# Sensors.net
KiCad netlist of a schematic drawn in Altium Designer
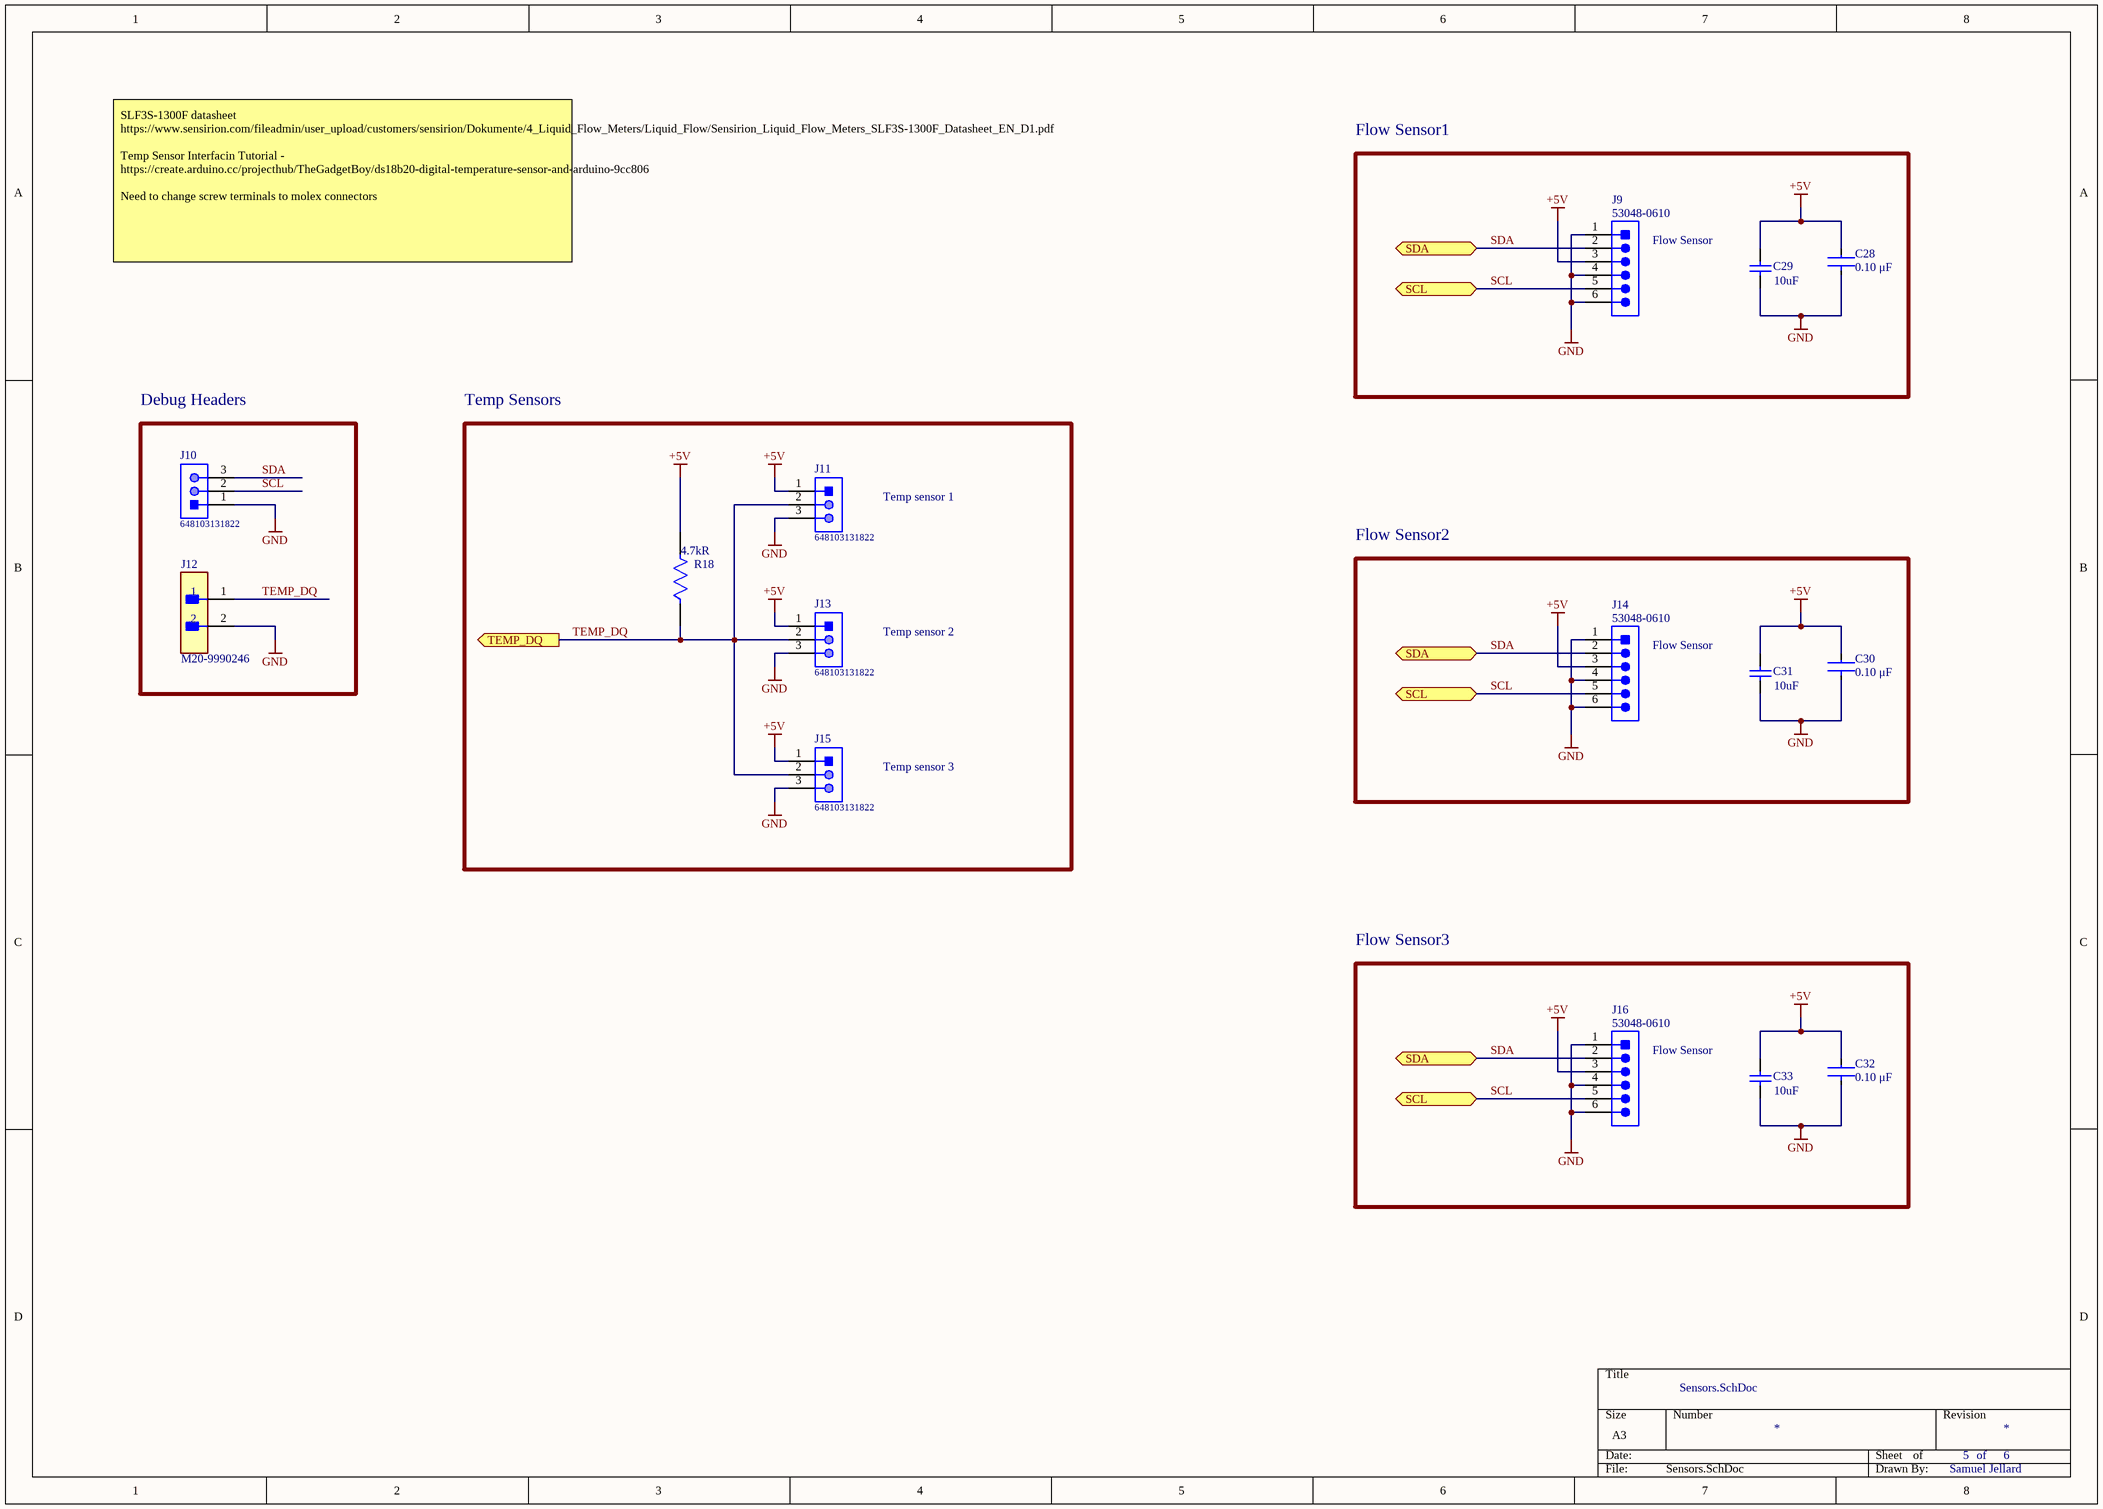
[diagram p0: Sensors.SchDoc]

(export (version "E")
  (design (tool "Eeschema 10.0.6"))
  (components
    (comp (ref "C28")
      (value "0.10 μF")
      (footprint "FP-C0603C-CF-MFG")
      (description "Multilayer Ceramic Capacitors (MLCC) - SMD/SMT 50volts 0.1uF X7R 10%")
      (fields (field (name "TOLERANCE") "0.1") (field (name "MANUFACTURER") "KEMET"))
      (libsource (lib "Altium Content Vault") (part "b4654b650e69147ec39a6b967a45e02"))
    )
    (comp (ref "C29")
      (value "10uF")
      (footprint "CAPC0603(1608)100_N")
      (description "CAP 10uF 6.3V ±20% 0603 (1608 Metric) Thickness 1mm SMD")
      (fields (field (name "TOLERANCE") "Â±20%") (field (name "Comment") "C0603C106M9PACTU"))
      (libsource (lib "Altium Content Vault") (part "CAP"))
    )
    (comp (ref "C30")
      (value "0.10 μF")
      (footprint "FP-C0603C-CF-MFG")
      (description "Multilayer Ceramic Capacitors (MLCC) - SMD/SMT 50volts 0.1uF X7R 10%")
      (fields (field (name "TOLERANCE") "0.1") (field (name "MANUFACTURER") "KEMET"))
      (libsource (lib "Altium Content Vault") (part "b4654b650e69147ec39a6b967a45e02"))
    )
    (comp (ref "C31")
      (value "10uF")
      (footprint "CAPC0603(1608)100_N")
      (description "CAP 10uF 6.3V ±20% 0603 (1608 Metric) Thickness 1mm SMD")
      (fields (field (name "TOLERANCE") "Â±20%") (field (name "Comment") "C0603C106M9PACTU"))
      (libsource (lib "Altium Content Vault") (part "CAP"))
    )
    (comp (ref "C32")
      (value "0.10 μF")
      (footprint "FP-C0603C-CF-MFG")
      (description "Multilayer Ceramic Capacitors (MLCC) - SMD/SMT 50volts 0.1uF X7R 10%")
      (fields (field (name "TOLERANCE") "0.1") (field (name "MANUFACTURER") "KEMET"))
      (libsource (lib "Altium Content Vault") (part "b4654b650e69147ec39a6b967a45e02"))
    )
    (comp (ref "C33")
      (value "10uF")
      (footprint "CAPC0603(1608)100_N")
      (description "CAP 10uF 6.3V ±20% 0603 (1608 Metric) Thickness 1mm SMD")
      (fields (field (name "TOLERANCE") "Â±20%") (field (name "Comment") "C0603C106M9PACTU"))
      (libsource (lib "Altium Content Vault") (part "CAP"))
    )
    (comp (ref "J9")
      (value "53048-0610")
      (footprint "MOLX-53048-0610_V")
      (fields (field (name "MANUFACTURER") "Molex"))
      (libsource (lib "Altium Content Vault") (part "CN-1P-M-R6"))
    )
    (comp (ref "J10")
      (value "648103131822")
      (footprint "648103131822")
      (description "Male Shrouded Header WR-WTB, SMT, Right Angled, pitch 1.5 mm, 1 x 3 position")
      (fields (field (name "MANUFACTURER") "Wurth Elektronik") (field (name "PUBLISHER") "WurthElektronik"))
      (libsource (lib "") (part "WE-CN-1P-M-R3_1"))
    )
    (comp (ref "J11")
      (value "648103131822")
      (footprint "648103131822")
      (description "Male Shrouded Header WR-WTB, SMT, Right Angled, pitch 1.5 mm, 1 x 3 position")
      (fields (field (name "MANUFACTURER") "Wurth Elektronik") (field (name "PUBLISHER") "WurthElektronik"))
      (libsource (lib "Altium Content Vault") (part "WE-CN-1P-M-R3"))
    )
    (comp (ref "J12")
      (value "M20-9990246")
      (footprint "FP-M20-9990246-MFG")
      (description "2.54mm (0.1\") Pitch SIL Vertical PC Tail Pin Header, 6.1mm mating pin height, tin, 2 contacts")
      (fields
        (field (name "OCTOPART") "https://octopart.com/m20-9990246-harwin-2590635")
        (field (name "MANUFACTURER") "Harwin")
      )
      (libsource (lib "Altium Content Vault") (part "3bc925449376181038e59eaffc5286c"))
    )
    (comp (ref "J13")
      (value "648103131822")
      (footprint "648103131822")
      (description "Male Shrouded Header WR-WTB, SMT, Right Angled, pitch 1.5 mm, 1 x 3 position")
      (fields (field (name "MANUFACTURER") "Wurth Elektronik") (field (name "PUBLISHER") "WurthElektronik"))
      (libsource (lib "Altium Content Vault") (part "WE-CN-1P-M-R3"))
    )
    (comp (ref "J14")
      (value "53048-0610")
      (footprint "MOLX-53048-0610_V")
      (fields (field (name "MANUFACTURER") "Molex"))
      (libsource (lib "Altium Content Vault") (part "CN-1P-M-R6"))
    )
    (comp (ref "J15")
      (value "648103131822")
      (footprint "648103131822")
      (description "Male Shrouded Header WR-WTB, SMT, Right Angled, pitch 1.5 mm, 1 x 3 position")
      (fields (field (name "MANUFACTURER") "Wurth Elektronik") (field (name "PUBLISHER") "WurthElektronik"))
      (libsource (lib "Altium Content Vault") (part "WE-CN-1P-M-R3"))
    )
    (comp (ref "J16")
      (value "53048-0610")
      (footprint "MOLX-53048-0610_V")
      (fields (field (name "MANUFACTURER") "Molex"))
      (libsource (lib "Altium Content Vault") (part "CN-1P-M-R6"))
    )
    (comp (ref "R18")
      (value "CRCW06034K70FKEA")
      (footprint "FP-CRCW0603-e3-IPC_A")
      (description "RES Thick Film, 4.7kΩ, 1%, 0.1W, 100ppm/°C, 0603")
      (fields (field (name "RESISTANCE") "4.7kR") (field (name "TOLERANCE") "1%"))
      (libsource (lib "Altium Content Vault") (part "1029c3af85768c4190bb7ad29bc67b5"))
    )
  )
  (nets
    (net (code "1") (name "+5V") (class "Default")
      (node (ref "C28") (pin "2") (pinfunction "2_2") (pintype "passive"))
      (node (ref "C29") (pin "2") (pinfunction "2_2") (pintype "passive"))
      (node (ref "C30") (pin "2") (pinfunction "2_2") (pintype "passive"))
      (node (ref "C31") (pin "2") (pinfunction "2_2") (pintype "passive"))
      (node (ref "C32") (pin "2") (pinfunction "2_2") (pintype "passive"))
      (node (ref "C33") (pin "2") (pinfunction "2_2") (pintype "passive"))
      (node (ref "J11") (pin "1") (pinfunction "1_1") (pintype "passive"))
      (node (ref "J13") (pin "1") (pinfunction "1_1") (pintype "passive"))
      (node (ref "J14") (pin "3") (pinfunction "3_3") (pintype "passive"))
      (node (ref "J15") (pin "1") (pinfunction "1_1") (pintype "passive"))
      (node (ref "J16") (pin "3") (pinfunction "3_3") (pintype "passive"))
      (node (ref "J9") (pin "3") (pinfunction "3_3") (pintype "passive"))
      (node (ref "R18") (pin "2") (pinfunction "2_2") (pintype "passive"))
    )
    (net (code "2") (name "/SCL") (class "Default")
      (node (ref "J10") (pin "2") (pinfunction "2_2") (pintype "passive"))
      (node (ref "J14") (pin "5") (pinfunction "5_5") (pintype "passive"))
      (node (ref "J16") (pin "5") (pinfunction "5_5") (pintype "passive"))
      (node (ref "J9") (pin "5") (pinfunction "5_5") (pintype "passive"))
    )
    (net (code "3") (name "/SDA") (class "Default")
      (node (ref "J10") (pin "3") (pinfunction "3_3") (pintype "passive"))
      (node (ref "J14") (pin "2") (pinfunction "2_2") (pintype "passive"))
      (node (ref "J16") (pin "2") (pinfunction "2_2") (pintype "passive"))
      (node (ref "J9") (pin "2") (pinfunction "2_2") (pintype "passive"))
    )
    (net (code "4") (name "/TEMP_DQ") (class "Default")
      (node (ref "J11") (pin "2") (pinfunction "2_2") (pintype "passive"))
      (node (ref "J12") (pin "1") (pinfunction "1_1") (pintype "passive"))
      (node (ref "J13") (pin "2") (pinfunction "2_2") (pintype "passive"))
      (node (ref "J15") (pin "2") (pinfunction "2_2") (pintype "passive"))
      (node (ref "R18") (pin "1") (pinfunction "1_1") (pintype "passive"))
    )
    (net (code "5") (name "GND") (class "Default")
      (node (ref "C28") (pin "1") (pinfunction "1_1") (pintype "passive"))
      (node (ref "C29") (pin "1") (pinfunction "1_1") (pintype "passive"))
      (node (ref "C30") (pin "1") (pinfunction "1_1") (pintype "passive"))
      (node (ref "C31") (pin "1") (pinfunction "1_1") (pintype "passive"))
      (node (ref "C32") (pin "1") (pinfunction "1_1") (pintype "passive"))
      (node (ref "C33") (pin "1") (pinfunction "1_1") (pintype "passive"))
      (node (ref "J10") (pin "1") (pinfunction "1_1") (pintype "passive"))
      (node (ref "J11") (pin "3") (pinfunction "3_3") (pintype "passive"))
      (node (ref "J12") (pin "2") (pinfunction "2_2") (pintype "passive"))
      (node (ref "J13") (pin "3") (pinfunction "3_3") (pintype "passive"))
      (node (ref "J14") (pin "1") (pinfunction "1_1") (pintype "passive"))
      (node (ref "J14") (pin "4") (pinfunction "4_4") (pintype "passive"))
      (node (ref "J14") (pin "6") (pinfunction "6_6") (pintype "passive"))
      (node (ref "J15") (pin "3") (pinfunction "3_3") (pintype "passive"))
      (node (ref "J16") (pin "1") (pinfunction "1_1") (pintype "passive"))
      (node (ref "J16") (pin "4") (pinfunction "4_4") (pintype "passive"))
      (node (ref "J16") (pin "6") (pinfunction "6_6") (pintype "passive"))
      (node (ref "J9") (pin "1") (pinfunction "1_1") (pintype "passive"))
      (node (ref "J9") (pin "4") (pinfunction "4_4") (pintype "passive"))
      (node (ref "J9") (pin "6") (pinfunction "6_6") (pintype "passive"))
    )
  )
)
